# UKU20710_power_board.net
KiCad netlist of a schematic drawn in Altium Designer
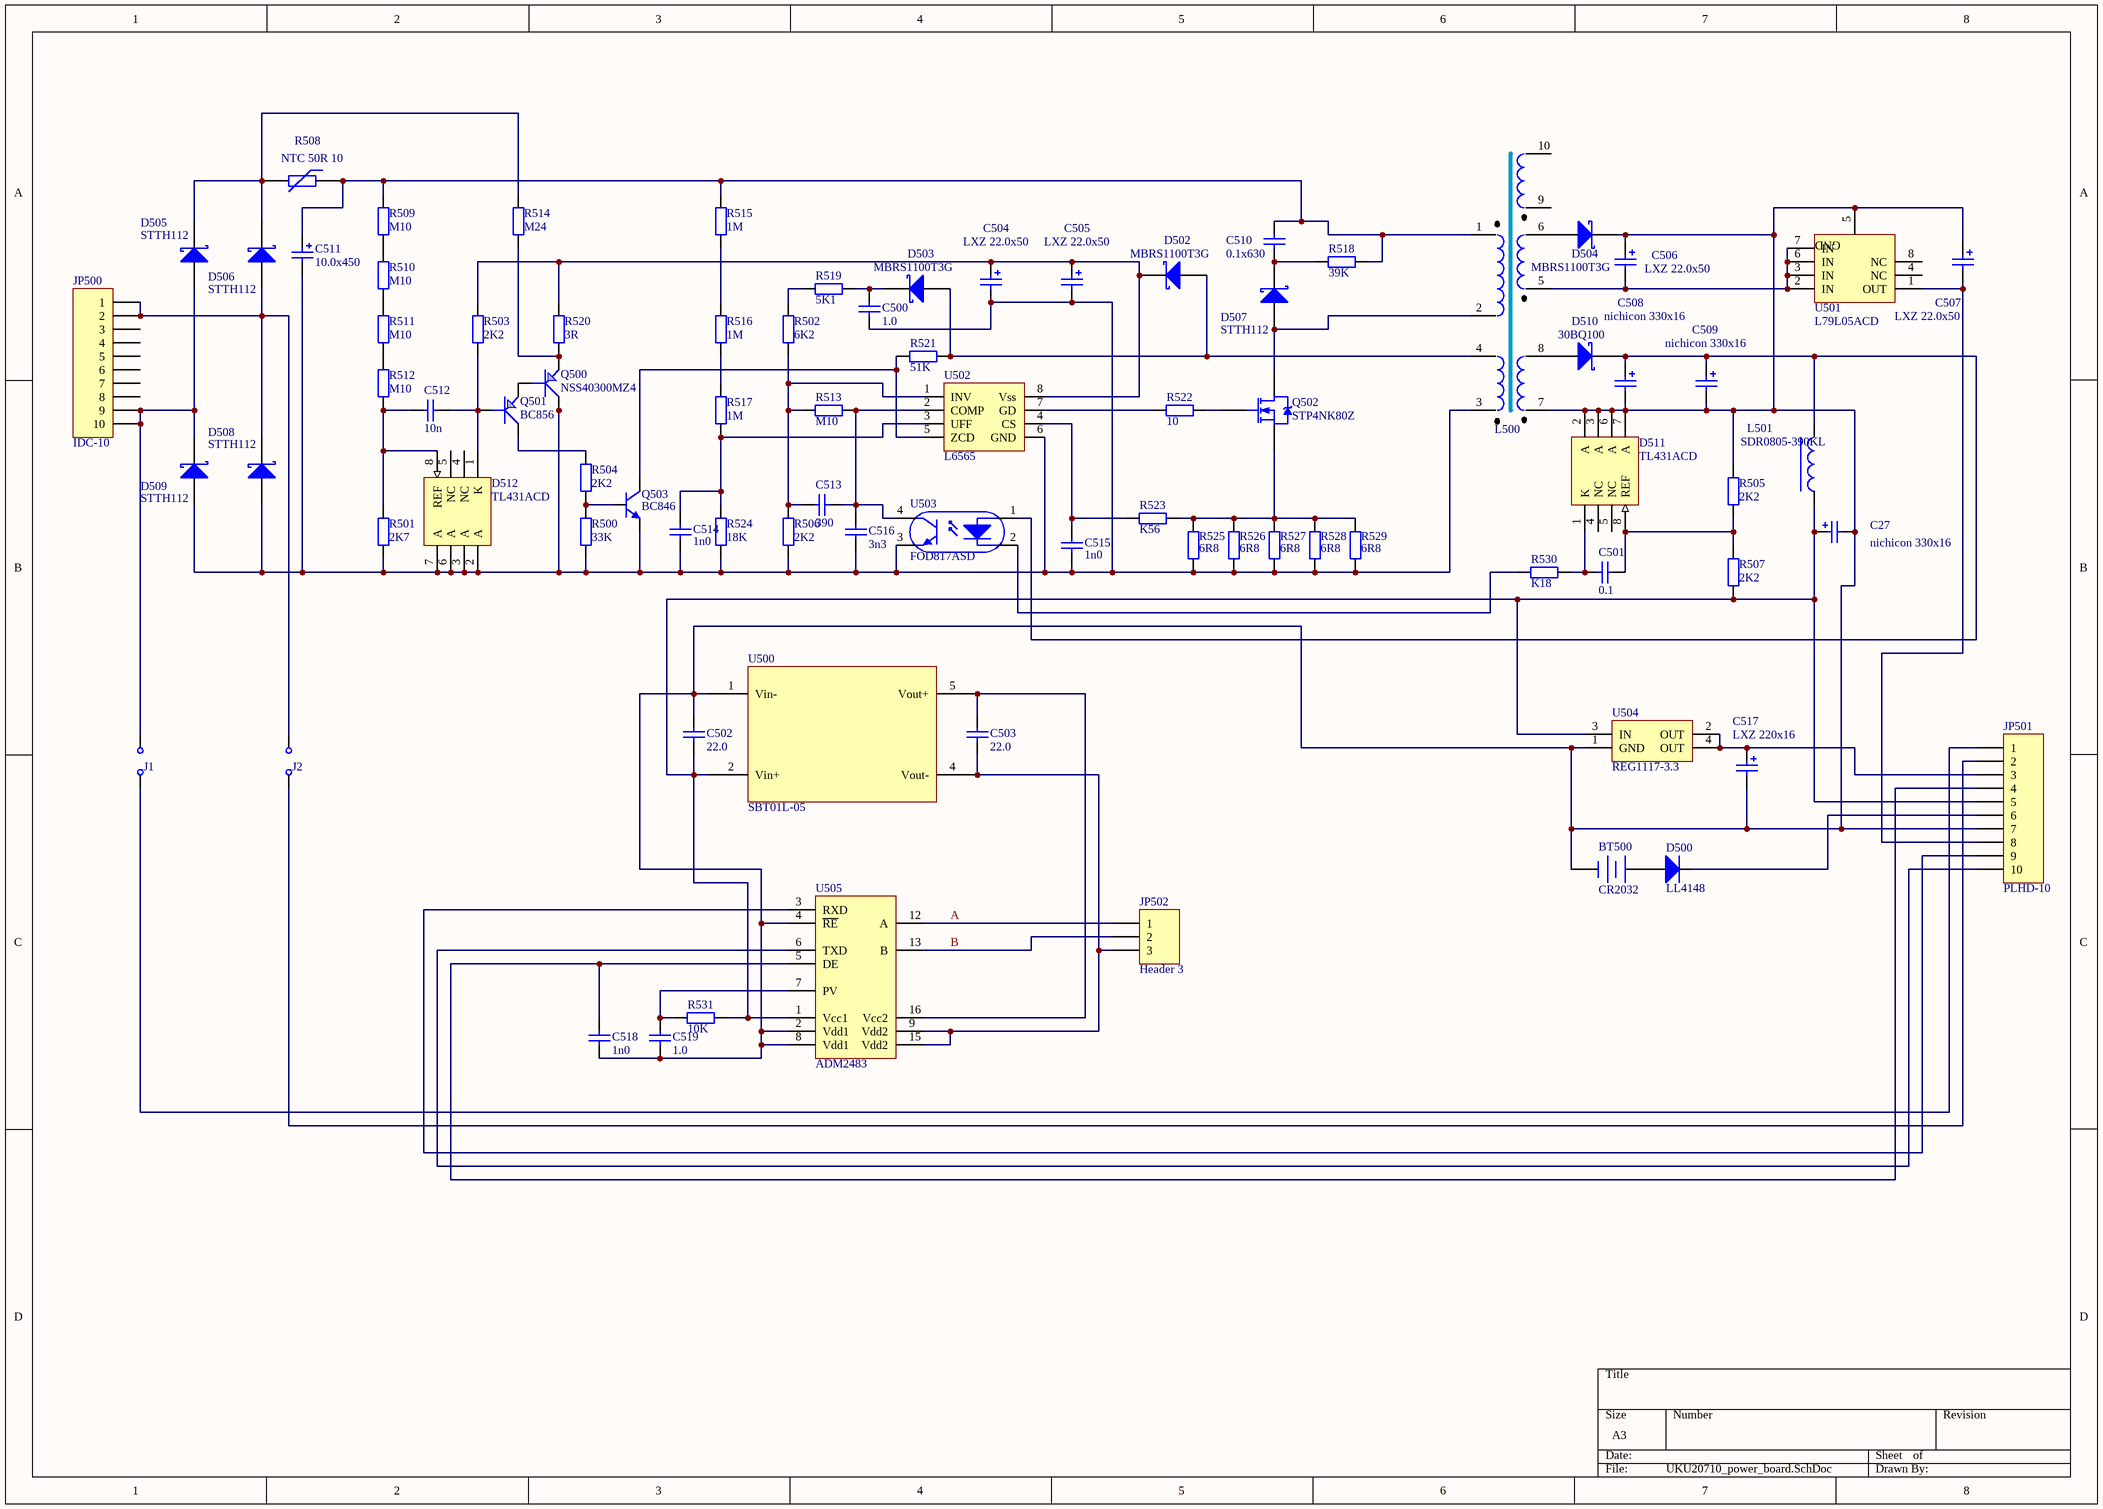
[diagram p0: UKU20710_power_board.SchDoc]

(export (version "E")
  (design (tool "Eeschema 10.0.6"))
  (components
    (comp (ref "BT500")
      (value "CR2032")
      (footprint "BAT_SUPP")
      (description "Multicell Battery")
      (fields (field (name "MANUFACTURER") "Generic Components") (field (name "PUBLISHER") "Altium Limited"))
      (libsource (lib "Miscellaneous Devices") (part "Battery"))
    )
    (comp (ref "C27")
      (value "nichicon 330x16")
      (footprint "el3")
      (description "Polarized Capacitor (Radial)")
      (fields (field (name "MANUFACTURER") "Generic Components") (field (name "PUBLISHER") "Altium Limited"))
      (libsource (lib "PAL") (part "Cap Pol1"))
    )
    (comp (ref "C500")
      (value "1.0")
      (footprint "_1206")
      (description "Capacitor (Semiconductor SIM Model)")
      (fields (field (name "MANUFACTURER") "Generic Components") (field (name "PUBLISHER") "Altium Limited"))
      (libsource (lib "Miscellaneous Devices") (part "Cap Semi"))
    )
    (comp (ref "C501")
      (value "0.1")
      (footprint "_1206")
      (description "Capacitor (Semiconductor SIM Model)")
      (fields (field (name "MANUFACTURER") "Generic Components") (field (name "PUBLISHER") "Altium Limited"))
      (libsource (lib "Miscellaneous Devices") (part "Cap Semi"))
    )
    (comp (ref "C502")
      (value "22.0")
      (footprint "_1206")
      (description "Capacitor (Semiconductor SIM Model)")
      (fields (field (name "MANUFACTURER") "Generic Components") (field (name "PUBLISHER") "Altium Limited"))
      (libsource (lib "Miscellaneous Devices") (part "Cap Semi"))
    )
    (comp (ref "C503")
      (value "22.0")
      (footprint "_1206")
      (description "Capacitor (Semiconductor SIM Model)")
      (fields (field (name "MANUFACTURER") "Generic Components") (field (name "PUBLISHER") "Altium Limited"))
      (libsource (lib "Miscellaneous Devices") (part "Cap Semi"))
    )
    (comp (ref "C504")
      (value "LXZ 22.0x50")
      (footprint "el3")
      (description "Polarized Capacitor (Radial)")
      (fields (field (name "MANUFACTURER") "Generic Components") (field (name "PUBLISHER") "Altium Limited"))
      (libsource (lib "PAL") (part "Cap Pol1"))
    )
    (comp (ref "C505")
      (value "LXZ 22.0x50")
      (footprint "el3")
      (description "Polarized Capacitor (Radial)")
      (fields (field (name "MANUFACTURER") "Generic Components") (field (name "PUBLISHER") "Altium Limited"))
      (libsource (lib "PAL") (part "Cap Pol1"))
    )
    (comp (ref "C506")
      (value "LXZ 22.0x50")
      (footprint "el3")
      (description "Polarized Capacitor (Radial)")
      (fields (field (name "MANUFACTURER") "Generic Components") (field (name "PUBLISHER") "Altium Limited"))
      (libsource (lib "PAL") (part "Cap Pol1"))
    )
    (comp (ref "C507")
      (value "LXZ 22.0x50")
      (footprint "el3")
      (description "Polarized Capacitor (Radial)")
      (fields (field (name "MANUFACTURER") "Generic Components") (field (name "PUBLISHER") "Altium Limited"))
      (libsource (lib "PAL") (part "Cap Pol1"))
    )
    (comp (ref "C508")
      (value "nichicon 330x16")
      (footprint "el3")
      (description "Polarized Capacitor (Radial)")
      (fields (field (name "MANUFACTURER") "Generic Components") (field (name "PUBLISHER") "Altium Limited"))
      (libsource (lib "PAL") (part "Cap Pol1"))
    )
    (comp (ref "C509")
      (value "nichicon 330x16")
      (footprint "el3")
      (description "Polarized Capacitor (Radial)")
      (fields (field (name "MANUFACTURER") "Generic Components") (field (name "PUBLISHER") "Altium Limited"))
      (libsource (lib "PAL") (part "Cap Pol1"))
    )
    (comp (ref "C510")
      (value "0.1x630")
      (footprint "c15")
      (description "Capacitor (Semiconductor SIM Model)")
      (fields (field (name "MANUFACTURER") "Generic Components") (field (name "PUBLISHER") "Altium Limited"))
      (libsource (lib "Miscellaneous Devices") (part "Cap Semi"))
    )
    (comp (ref "C511")
      (value "10.0x450")
      (footprint "el_15_25_h")
      (description "Polarized Capacitor (Radial)")
      (fields (field (name "MANUFACTURER") "Generic Components") (field (name "PUBLISHER") "Altium Limited"))
      (libsource (lib "PAL") (part "Cap Pol1"))
    )
    (comp (ref "C512")
      (value "10n")
      (footprint "_1206")
      (description "Capacitor (Semiconductor SIM Model)")
      (fields (field (name "MANUFACTURER") "Generic Components") (field (name "PUBLISHER") "Altium Limited"))
      (libsource (lib "Miscellaneous Devices") (part "Cap Semi"))
    )
    (comp (ref "C513")
      (value "390")
      (footprint "_1206")
      (description "Capacitor (Semiconductor SIM Model)")
      (fields (field (name "MANUFACTURER") "Generic Components") (field (name "PUBLISHER") "Altium Limited"))
      (libsource (lib "Miscellaneous Devices") (part "Cap Semi"))
    )
    (comp (ref "C514")
      (value "1n0")
      (footprint "_1206")
      (description "Capacitor (Semiconductor SIM Model)")
      (fields (field (name "MANUFACTURER") "Generic Components") (field (name "PUBLISHER") "Altium Limited"))
      (libsource (lib "Miscellaneous Devices") (part "Cap Semi"))
    )
    (comp (ref "C515")
      (value "1n0")
      (footprint "_1206")
      (description "Capacitor (Semiconductor SIM Model)")
      (fields (field (name "MANUFACTURER") "Generic Components") (field (name "PUBLISHER") "Altium Limited"))
      (libsource (lib "Miscellaneous Devices") (part "Cap Semi"))
    )
    (comp (ref "C516")
      (value "3n3")
      (footprint "_1206")
      (description "Capacitor (Semiconductor SIM Model)")
      (fields (field (name "MANUFACTURER") "Generic Components") (field (name "PUBLISHER") "Altium Limited"))
      (libsource (lib "Miscellaneous Devices") (part "Cap Semi"))
    )
    (comp (ref "C517")
      (value "LXZ 220x16")
      (footprint "el3")
      (description "Polarized Capacitor (Radial)")
      (fields (field (name "MANUFACTURER") "Generic Components") (field (name "PUBLISHER") "Altium Limited"))
      (libsource (lib "PAL") (part "Cap Pol1"))
    )
    (comp (ref "C518")
      (value "1n0")
      (footprint "_1206")
      (description "Capacitor (Semiconductor SIM Model)")
      (fields (field (name "MANUFACTURER") "Generic Components") (field (name "PUBLISHER") "Altium Limited"))
      (libsource (lib "Miscellaneous Devices") (part "Cap Semi"))
    )
    (comp (ref "C519")
      (value "1.0")
      (footprint "_1206")
      (description "Capacitor (Semiconductor SIM Model)")
      (fields (field (name "MANUFACTURER") "Generic Components") (field (name "PUBLISHER") "Altium Limited"))
      (libsource (lib "Miscellaneous Devices") (part "Cap Semi"))
    )
    (comp (ref "D500")
      (value "LL4148")
      (footprint "_1206d")
      (description "Default Diode")
      (fields (field (name "MANUFACTURER") "Generic Components") (field (name "PUBLISHER") "Altium Limited"))
      (libsource (lib "PAL") (part "Diode"))
    )
    (comp (ref "D502")
      (value "MBRS1100T3G")
      (footprint "D_6_3")
      (description "Schottky Rectifier")
      (fields
        (field (name "MANUFACTURER") "International Rectifier")
        (field (name "PUBLISHER") "Altium Limited")
      )
      (libsource (lib "IR Discrete Diode") (part "10BQ015"))
    )
    (comp (ref "D503")
      (value "MBRS1100T3G")
      (footprint "D_6_3")
      (description "Schottky Rectifier")
      (fields
        (field (name "MANUFACTURER") "International Rectifier")
        (field (name "PUBLISHER") "Altium Limited")
      )
      (libsource (lib "IR Discrete Diode") (part "10BQ015"))
    )
    (comp (ref "D504")
      (value "MBRS1100T3G")
      (footprint "D_6_3")
      (description "Schottky Rectifier")
      (fields
        (field (name "MANUFACTURER") "International Rectifier")
        (field (name "PUBLISHER") "Altium Limited")
      )
      (libsource (lib "IR Discrete Diode") (part "10BQ015"))
    )
    (comp (ref "D505")
      (value "STTH112")
      (footprint "D_6_3")
      (description "Schottky Diode")
      (fields
        (field (name "MANUFACTURER") "International Rectifier")
        (field (name "PUBLISHER") "Altium Limited")
      )
      (libsource (lib "IR Discrete Diode") (part "10BQ015"))
    )
    (comp (ref "D506")
      (value "STTH112")
      (footprint "D_6_3")
      (description "Schottky Diode")
      (fields
        (field (name "MANUFACTURER") "International Rectifier")
        (field (name "PUBLISHER") "Altium Limited")
      )
      (libsource (lib "IR Discrete Diode") (part "10BQ015"))
    )
    (comp (ref "D507")
      (value "STTH112")
      (footprint "D_6_3")
      (description "Schottky Diode")
      (fields
        (field (name "MANUFACTURER") "International Rectifier")
        (field (name "PUBLISHER") "Altium Limited")
      )
      (libsource (lib "IR Discrete Diode") (part "10BQ015"))
    )
    (comp (ref "D508")
      (value "STTH112")
      (footprint "D_6_3")
      (description "Schottky Diode")
      (fields
        (field (name "MANUFACTURER") "International Rectifier")
        (field (name "PUBLISHER") "Altium Limited")
      )
      (libsource (lib "IR Discrete Diode") (part "10BQ015"))
    )
    (comp (ref "D509")
      (value "STTH112")
      (footprint "D_6_3")
      (description "Schottky Diode")
      (fields
        (field (name "MANUFACTURER") "International Rectifier")
        (field (name "PUBLISHER") "Altium Limited")
      )
      (libsource (lib "IR Discrete Diode") (part "10BQ015"))
    )
    (comp (ref "D510")
      (value "30BQ100")
      (footprint "30BQ100")
      (description "Schottky Rectifier")
      (fields
        (field (name "MANUFACTURER") "International Rectifier")
        (field (name "PUBLISHER") "Altium Limited")
      )
      (libsource (lib "IR Discrete Diode") (part "10BQ015"))
    )
    (comp (ref "D511")
      (value "TL431ACD")
      (footprint "SO-G8")
      (description "Programmable Precision Reference")
      (fields (field (name "MANUFACTURER") "Motorola") (field (name "PUBLISHER") "Altium Limited"))
      (libsource (lib "") (part "TL431ACD_1"))
    )
    (comp (ref "D512")
      (value "TL431ACD")
      (footprint "SO-G8")
      (description "Programmable Precision Reference")
      (fields (field (name "MANUFACTURER") "Motorola") (field (name "PUBLISHER") "Altium Limited"))
      (libsource (lib "Motorola Power Management Voltage Reference") (part "TL431ACD"))
    )
    (comp (ref "J1")
      (value "~")
      (footprint "BT5-2")
      (description "Switch")
      (fields (field (name "MANUFACTURER") "Generic Components") (field (name "PUBLISHER") "Altium Limited"))
      (libsource (lib "PAL") (part "JMP"))
    )
    (comp (ref "J2")
      (value "~")
      (footprint "BT5-2")
      (description "Switch")
      (fields (field (name "MANUFACTURER") "Generic Components") (field (name "PUBLISHER") "Altium Limited"))
      (libsource (lib "PAL") (part "JMP"))
    )
    (comp (ref "JP500")
      (value "IDC-10")
      (footprint "HDR2X5")
      (description "Header, 10-Pin")
      (fields (field (name "MANUFACTURER") "Generic Components") (field (name "PUBLISHER") "Altium Limited"))
      (libsource (lib "") (part "Header 10_1"))
    )
    (comp (ref "JP501")
      (value "PLHD-10")
      (footprint "HDR2X5")
      (description "Header, 10-Pin")
      (fields (field (name "MANUFACTURER") "Generic Components") (field (name "PUBLISHER") "Altium Limited"))
      (libsource (lib "Miscellaneous Connectors") (part "Header 10"))
    )
    (comp (ref "JP502")
      (value "Header 3")
      (footprint "2EDG-5.08-3P")
      (description "Header, 3-Pin")
      (fields (field (name "MANUFACTURER") "Generic Components") (field (name "PUBLISHER") "Altium Limited"))
      (libsource (lib "Miscellaneous Connectors") (part "Header 3"))
    )
    (comp (ref "L500")
      (value "L220-K10")
      (footprint "trans_ring1")
      (description "Дроссель")
      (libsource (lib "PAL") (part "L1_dc_2"))
    )
    (comp (ref "L501")
      (value "SDR0805-390KL")
      (footprint "L10x10")
      (description "Magnetic-Core Inductor")
      (fields (field (name "MANUFACTURER") "Generic Components") (field (name "PUBLISHER") "Altium Limited"))
      (libsource (lib "PAL") (part "Inductor Konstr 2"))
    )
    (comp (ref "Q500")
      (value "NSS40300MZ4")
      (footprint "DSO-G3")
      (libsource (lib "PAL") (part "NSS40300MZ4"))
    )
    (comp (ref "Q501")
      (value "BC856")
      (footprint "SO-G3")
      (description "Bipolar transistor")
      (libsource (lib "MAIN") (part "GT109"))
    )
    (comp (ref "Q502")
      (value "STP4NK80Z")
      (footprint "TO220_h")
      (description "N-Channel Power MOSFET")
      (fields (field (name "MANUFACTURER") "Generic Components") (field (name "PUBLISHER") "Altium Limited"))
      (libsource (lib "Miscellaneous Devices") (part "NMOS-2"))
    )
    (comp (ref "Q503")
      (value "BC846")
      (footprint "SO-G3")
      (description "General Purpose Transistor NPN Silicon")
      (fields (field (name "MANUFACTURER") "Motorola") (field (name "PUBLISHER") "Altium Limited"))
      (libsource (lib "PAL") (part "BC847ALT1"))
    )
    (comp (ref "R500")
      (value "33K")
      (footprint "_1206")
      (description "Resistor")
      (fields (field (name "MANUFACTURER") "Generic Components") (field (name "PUBLISHER") "Altium Limited"))
      (libsource (lib "") (part "Res2_1"))
    )
    (comp (ref "R501")
      (value "2K7")
      (footprint "_1206")
      (description "Resistor")
      (fields (field (name "MANUFACTURER") "Generic Components") (field (name "PUBLISHER") "Altium Limited"))
      (libsource (lib "") (part "Res2_1"))
    )
    (comp (ref "R502")
      (value "6K2")
      (footprint "_1206")
      (description "Resistor")
      (fields (field (name "MANUFACTURER") "Generic Components") (field (name "PUBLISHER") "Altium Limited"))
      (libsource (lib "") (part "Res2_1"))
    )
    (comp (ref "R503")
      (value "2K2")
      (footprint "_1206")
      (description "Resistor")
      (fields (field (name "MANUFACTURER") "Generic Components") (field (name "PUBLISHER") "Altium Limited"))
      (libsource (lib "") (part "Res2_1"))
    )
    (comp (ref "R504")
      (value "2K2")
      (footprint "_1206")
      (description "Resistor")
      (fields (field (name "MANUFACTURER") "Generic Components") (field (name "PUBLISHER") "Altium Limited"))
      (libsource (lib "") (part "Res2_1"))
    )
    (comp (ref "R505")
      (value "2K2")
      (footprint "_1206")
      (description "Resistor")
      (fields (field (name "MANUFACTURER") "Generic Components") (field (name "PUBLISHER") "Altium Limited"))
      (libsource (lib "") (part "Res2_1"))
    )
    (comp (ref "R506")
      (value "2K2")
      (footprint "_1206")
      (description "Resistor")
      (fields (field (name "MANUFACTURER") "Generic Components") (field (name "PUBLISHER") "Altium Limited"))
      (libsource (lib "") (part "Res2_1"))
    )
    (comp (ref "R507")
      (value "2K2")
      (footprint "_1206")
      (description "Resistor")
      (fields (field (name "MANUFACTURER") "Generic Components") (field (name "PUBLISHER") "Altium Limited"))
      (libsource (lib "") (part "Res2_1"))
    )
    (comp (ref "R508")
      (value "NTC 50R 10")
      (footprint "JVR07N")
      (description "Varistor (Voltage-Sensitive Resistor)")
      (fields (field (name "MANUFACTURER") "Generic Components") (field (name "PUBLISHER") "Altium Limited"))
      (libsource (lib "Miscellaneous Devices") (part "Res Varistor"))
    )
    (comp (ref "R509")
      (value "M10")
      (footprint "_1206")
      (description "Resistor")
      (fields (field (name "MANUFACTURER") "Generic Components") (field (name "PUBLISHER") "Altium Limited"))
      (libsource (lib "") (part "Res2_1"))
    )
    (comp (ref "R510")
      (value "M10")
      (footprint "_1206")
      (description "Resistor")
      (fields (field (name "MANUFACTURER") "Generic Components") (field (name "PUBLISHER") "Altium Limited"))
      (libsource (lib "") (part "Res2_1"))
    )
    (comp (ref "R511")
      (value "M10")
      (footprint "_1206")
      (description "Resistor")
      (fields (field (name "MANUFACTURER") "Generic Components") (field (name "PUBLISHER") "Altium Limited"))
      (libsource (lib "") (part "Res2_1"))
    )
    (comp (ref "R512")
      (value "M10")
      (footprint "_1206")
      (description "Resistor")
      (fields (field (name "MANUFACTURER") "Generic Components") (field (name "PUBLISHER") "Altium Limited"))
      (libsource (lib "") (part "Res2_1"))
    )
    (comp (ref "R513")
      (value "M10")
      (footprint "_1206")
      (description "Resistor")
      (fields (field (name "MANUFACTURER") "Generic Components") (field (name "PUBLISHER") "Altium Limited"))
      (libsource (lib "") (part "Res2_2"))
    )
    (comp (ref "R514")
      (value "M24")
      (footprint "AXIAL-0.7")
      (description "Resistor")
      (fields (field (name "MANUFACTURER") "Generic Components") (field (name "PUBLISHER") "Altium Limited"))
      (libsource (lib "") (part "Res2_1"))
    )
    (comp (ref "R515")
      (value "1M")
      (footprint "_1206")
      (description "Resistor")
      (fields (field (name "MANUFACTURER") "Generic Components") (field (name "PUBLISHER") "Altium Limited"))
      (libsource (lib "") (part "Res2_1"))
    )
    (comp (ref "R516")
      (value "1M")
      (footprint "_1206")
      (description "Resistor")
      (fields (field (name "MANUFACTURER") "Generic Components") (field (name "PUBLISHER") "Altium Limited"))
      (libsource (lib "") (part "Res2_1"))
    )
    (comp (ref "R517")
      (value "1M")
      (footprint "_1206")
      (description "Resistor")
      (fields (field (name "MANUFACTURER") "Generic Components") (field (name "PUBLISHER") "Altium Limited"))
      (libsource (lib "") (part "Res2_1"))
    )
    (comp (ref "R518")
      (value "39K")
      (footprint "AXIAL-0.7")
      (description "Resistor")
      (fields (field (name "MANUFACTURER") "Generic Components") (field (name "PUBLISHER") "Altium Limited"))
      (libsource (lib "") (part "Res2_2"))
    )
    (comp (ref "R519")
      (value "5K1")
      (footprint "_1206")
      (description "Resistor")
      (fields (field (name "MANUFACTURER") "Generic Components") (field (name "PUBLISHER") "Altium Limited"))
      (libsource (lib "") (part "Res2_2"))
    )
    (comp (ref "R520")
      (value "3R")
      (footprint "_1206")
      (description "Resistor")
      (fields (field (name "MANUFACTURER") "Generic Components") (field (name "PUBLISHER") "Altium Limited"))
      (libsource (lib "") (part "Res2_1"))
    )
    (comp (ref "R521")
      (value "51K")
      (footprint "_1206")
      (description "Resistor")
      (fields (field (name "MANUFACTURER") "Generic Components") (field (name "PUBLISHER") "Altium Limited"))
      (libsource (lib "") (part "Res2_2"))
    )
    (comp (ref "R522")
      (value "10")
      (footprint "_1206")
      (description "Resistor")
      (fields (field (name "MANUFACTURER") "Generic Components") (field (name "PUBLISHER") "Altium Limited"))
      (libsource (lib "") (part "Res2_2"))
    )
    (comp (ref "R523")
      (value "K56")
      (footprint "_1206")
      (description "Resistor")
      (fields (field (name "MANUFACTURER") "Generic Components") (field (name "PUBLISHER") "Altium Limited"))
      (libsource (lib "") (part "Res2_2"))
    )
    (comp (ref "R524")
      (value "18K")
      (footprint "_1206")
      (description "Resistor")
      (fields (field (name "MANUFACTURER") "Generic Components") (field (name "PUBLISHER") "Altium Limited"))
      (libsource (lib "") (part "Res2_1"))
    )
    (comp (ref "R525")
      (value "6R8")
      (footprint "_1206")
      (description "Resistor")
      (fields (field (name "MANUFACTURER") "Generic Components") (field (name "PUBLISHER") "Altium Limited"))
      (libsource (lib "Miscellaneous Devices") (part "Res2"))
    )
    (comp (ref "R526")
      (value "6R8")
      (footprint "_1206")
      (description "Resistor")
      (fields (field (name "MANUFACTURER") "Generic Components") (field (name "PUBLISHER") "Altium Limited"))
      (libsource (lib "Miscellaneous Devices") (part "Res2"))
    )
    (comp (ref "R527")
      (value "6R8")
      (footprint "_1206")
      (description "Resistor")
      (fields (field (name "MANUFACTURER") "Generic Components") (field (name "PUBLISHER") "Altium Limited"))
      (libsource (lib "Miscellaneous Devices") (part "Res2"))
    )
    (comp (ref "R528")
      (value "6R8")
      (footprint "_1206")
      (description "Resistor")
      (fields (field (name "MANUFACTURER") "Generic Components") (field (name "PUBLISHER") "Altium Limited"))
      (libsource (lib "Miscellaneous Devices") (part "Res2"))
    )
    (comp (ref "R529")
      (value "6R8")
      (footprint "_1206")
      (description "Resistor")
      (fields (field (name "MANUFACTURER") "Generic Components") (field (name "PUBLISHER") "Altium Limited"))
      (libsource (lib "Miscellaneous Devices") (part "Res2"))
    )
    (comp (ref "R530")
      (value "K18")
      (footprint "_1206")
      (description "Resistor")
      (fields (field (name "MANUFACTURER") "Generic Components") (field (name "PUBLISHER") "Altium Limited"))
      (libsource (lib "") (part "Res2_2"))
    )
    (comp (ref "R531")
      (value "10K")
      (footprint "_1206")
      (description "Resistor")
      (fields (field (name "MANUFACTURER") "Generic Components") (field (name "PUBLISHER") "Altium Limited"))
      (libsource (lib "") (part "Res2_2"))
    )
    (comp (ref "U500") (value "SBT01L-05") (footprint "SBT01DET01") (libsource (lib "PAL") (part "SBT01L")))
    (comp (ref "U501")
      (value "L79L05ACD")
      (footprint "SO-G8")
      (description "Negative Voltage Regulator")
      (fields (field (name "MANUFACTURER") "ST-Microelectronics") (field (name "PUBLISHER") "Altium Limited"))
      (libsource (lib "ST Power Mgt Voltage Regulator") (part "L79L05ACD"))
    )
    (comp (ref "U502") (value "L6565") (footprint "so-g8") (libsource (lib "PAL") (part "L6565")))
    (comp (ref "U503") (value "FOD817ASD") (footprint "FOD817ASD") (libsource (lib "PAL") (part "F00817ASD")))
    (comp (ref "U504")
      (value "REG1117-3.3")
      (footprint "DSO-G3")
      (description "800mA and 1A Low Dropout Positive Regulator 2.85V, 3.3V, 5V, and Adjustable")
      (fields (field (name "MANUFACTURER") "Burr-Brown") (field (name "PUBLISHER") "Altium Limited"))
      (libsource (lib "BB Power Mgt Voltage Regulator") (part "REG1117-3.3"))
    )
    (comp (ref "U505") (value "ADM2483") (footprint "SO-G16/D10.4") (libsource (lib "PAL") (part "ADM2483")))
  )
  (nets
    (net (code "1") (name "/A") (class "Default")
      (node (ref "JP502") (pin "1") (pinfunction "1_1") (pintype "passive"))
      (node (ref "U505") (pin "12") (pinfunction "A_12") (pintype "passive"))
    )
    (net (code "2") (name "/B") (class "Default")
      (node (ref "JP502") (pin "2") (pinfunction "2_2") (pintype "passive"))
      (node (ref "U505") (pin "13") (pinfunction "B_13") (pintype "passive"))
    )
    (net (code "3") (name "Net-(BT500-+)") (class "Default")
      (node (ref "BT500") (pin "1") (pinfunction "+_1") (pintype "passive"))
      (node (ref "D500") (pin "1") (pinfunction "A_1") (pintype "passive"))
    )
    (net (code "4") (name "Net-(BT500--)") (class "Default")
      (node (ref "BT500") (pin "2") (pinfunction "-_2") (pintype "passive"))
      (node (ref "C27") (pin "2") (pinfunction "2_2") (pintype "passive"))
      (node (ref "C502") (pin "1") (pinfunction "1_1") (pintype "passive"))
      (node (ref "C506") (pin "1") (pinfunction "1_1") (pintype "passive"))
      (node (ref "C507") (pin "1") (pinfunction "1_1") (pintype "passive"))
      (node (ref "C508") (pin "2") (pinfunction "2_2") (pintype "passive"))
      (node (ref "C509") (pin "2") (pinfunction "2_2") (pintype "passive"))
      (node (ref "C517") (pin "2") (pinfunction "2_2") (pintype "passive"))
      (node (ref "C518") (pin "1") (pinfunction "1_1") (pintype "passive"))
      (node (ref "C519") (pin "1") (pinfunction "1_1") (pintype "passive"))
      (node (ref "D504") (pin "2") (pinfunction "K_2") (pintype "passive"))
      (node (ref "D511") (pin "2") (pinfunction "A_2") (pintype "passive"))
      (node (ref "D511") (pin "3") (pinfunction "A_3") (pintype "passive"))
      (node (ref "D511") (pin "6") (pinfunction "A_6") (pintype "passive"))
      (node (ref "D511") (pin "7") (pinfunction "A_7") (pintype "passive"))
      (node (ref "JP501") (pin "7") (pinfunction "7_7") (pintype "passive"))
      (node (ref "L500") (pin "7") (pintype "passive"))
      (node (ref "R505") (pin "2") (pinfunction "2_2") (pintype "passive"))
      (node (ref "U500") (pin "1") (pinfunction "Vin-_1") (pintype "passive"))
      (node (ref "U501") (pin "5") (pinfunction "GND_5") (pintype "power_in"))
      (node (ref "U504") (pin "1") (pinfunction "GND_1") (pintype "power_in"))
      (node (ref "U505") (pin "2") (pinfunction "Vdd1_2") (pintype "passive"))
      (node (ref "U505") (pin "4") (pinfunction "~{RE}_4") (pintype "passive"))
      (node (ref "U505") (pin "8") (pinfunction "Vdd1_8") (pintype "passive"))
    )
    (net (code "5") (name "Net-(C506-Pad2)") (class "Default")
      (node (ref "C506") (pin "2") (pinfunction "2_2") (pintype "passive"))
      (node (ref "L500") (pin "5") (pintype "passive"))
      (node (ref "U501") (pin "2") (pinfunction "IN_2") (pintype "power_in"))
      (node (ref "U501") (pin "3") (pinfunction "IN_3") (pintype "power_in"))
      (node (ref "U501") (pin "6") (pinfunction "IN_6") (pintype "power_in"))
      (node (ref "U501") (pin "7") (pinfunction "IN_7") (pintype "power_in"))
    )
    (net (code "6") (name "Net-(C510-Pad2)") (class "Default")
      (node (ref "C510") (pin "2") (pinfunction "2_2") (pintype "passive"))
      (node (ref "C511") (pin "1") (pinfunction "1_1") (pintype "passive"))
      (node (ref "L500") (pin "1") (pintype "passive"))
      (node (ref "R508") (pin "1") (pinfunction "1_1") (pintype "passive"))
      (node (ref "R509") (pin "2") (pinfunction "2_2") (pintype "passive"))
      (node (ref "R515") (pin "2") (pinfunction "2_2") (pintype "passive"))
      (node (ref "R518") (pin "1") (pinfunction "1_1") (pintype "passive"))
    )
    (net (code "7") (name "Net-(C517-Pad1)") (class "Default")
      (node (ref "C517") (pin "1") (pinfunction "1_1") (pintype "passive"))
      (node (ref "JP501") (pin "3") (pinfunction "3_3") (pintype "passive"))
      (node (ref "U504") (pin "2") (pinfunction "OUT_2") (pintype "power_in"))
      (node (ref "U504") (pin "4") (pinfunction "OUT_4") (pintype "power_in"))
    )
    (net (code "8") (name "Net-(D500-K)") (class "Default")
      (node (ref "D500") (pin "2") (pinfunction "K_2") (pintype "passive"))
      (node (ref "JP501") (pin "6") (pinfunction "6_6") (pintype "passive"))
    )
    (net (code "9") (name "Net-(D502-A)") (class "Default")
      (node (ref "D502") (pin "1") (pinfunction "A_1") (pintype "passive"))
      (node (ref "D503") (pin "1") (pinfunction "A_1") (pintype "passive"))
      (node (ref "L500") (pin "4") (pintype "passive"))
      (node (ref "R521") (pin "1") (pinfunction "1_1") (pintype "passive"))
    )
    (net (code "10") (name "Net-(D502-K)") (class "Default")
      (node (ref "C504") (pin "1") (pinfunction "1_1") (pintype "passive"))
      (node (ref "C505") (pin "1") (pinfunction "1_1") (pintype "passive"))
      (node (ref "D502") (pin "2") (pinfunction "K_2") (pintype "passive"))
      (node (ref "R503") (pin "2") (pinfunction "2_2") (pintype "passive"))
      (node (ref "R520") (pin "2") (pinfunction "2_2") (pintype "passive"))
      (node (ref "U502") (pin "8") (pinfunction "Vss_8") (pintype "passive"))
    )
    (net (code "11") (name "Net-(D503-K)") (class "Default")
      (node (ref "C500") (pin "2") (pinfunction "2_2") (pintype "passive"))
      (node (ref "D503") (pin "2") (pinfunction "K_2") (pintype "passive"))
      (node (ref "R519") (pin "1") (pinfunction "1_1") (pintype "passive"))
    )
    (net (code "12") (name "Net-(D504-A)") (class "Default")
      (node (ref "D504") (pin "1") (pinfunction "A_1") (pintype "passive"))
      (node (ref "L500") (pin "6") (pintype "passive"))
    )
    (net (code "13") (name "Net-(D505-A)") (class "Default")
      (node (ref "D505") (pin "1") (pinfunction "A_1") (pintype "passive"))
      (node (ref "D509") (pin "2") (pinfunction "K_2") (pintype "passive"))
      (node (ref "J1") (pin "2") (pinfunction "2_2") (pintype "passive"))
      (node (ref "JP500") (pin "10") (pinfunction "10_10") (pintype "passive"))
      (node (ref "JP500") (pin "9") (pinfunction "9_9") (pintype "passive"))
    )
    (net (code "14") (name "Net-(D505-K)") (class "Default")
      (node (ref "D505") (pin "2") (pinfunction "K_2") (pintype "passive"))
      (node (ref "D506") (pin "2") (pinfunction "K_2") (pintype "passive"))
      (node (ref "R508") (pin "2") (pinfunction "2_2") (pintype "passive"))
      (node (ref "R514") (pin "2") (pinfunction "2_2") (pintype "passive"))
    )
    (net (code "15") (name "Net-(D506-A)") (class "Default")
      (node (ref "D506") (pin "1") (pinfunction "A_1") (pintype "passive"))
      (node (ref "D508") (pin "2") (pinfunction "K_2") (pintype "passive"))
      (node (ref "J2") (pin "2") (pinfunction "2_2") (pintype "passive"))
      (node (ref "JP500") (pin "1") (pinfunction "1_1") (pintype "passive"))
      (node (ref "JP500") (pin "2") (pinfunction "2_2") (pintype "passive"))
    )
    (net (code "16") (name "Net-(D507-A)") (class "Default")
      (node (ref "D507") (pin "1") (pinfunction "A_1") (pintype "passive"))
      (node (ref "L500") (pin "2") (pintype "passive"))
      (node (ref "Q502") (pin "2") (pinfunction "D_2") (pintype "passive"))
    )
    (net (code "17") (name "Net-(D507-K)") (class "Default")
      (node (ref "C510") (pin "1") (pinfunction "1_1") (pintype "passive"))
      (node (ref "D507") (pin "2") (pinfunction "K_2") (pintype "passive"))
      (node (ref "R518") (pin "2") (pinfunction "2_2") (pintype "passive"))
    )
    (net (code "18") (name "Net-(D508-A)") (class "Default")
      (node (ref "C500") (pin "1") (pinfunction "1_1") (pintype "passive"))
      (node (ref "C504") (pin "2") (pinfunction "2_2") (pintype "passive"))
      (node (ref "C505") (pin "2") (pinfunction "2_2") (pintype "passive"))
      (node (ref "C511") (pin "2") (pinfunction "2_2") (pintype "passive"))
      (node (ref "C514") (pin "2") (pinfunction "2_2") (pintype "passive"))
      (node (ref "C515") (pin "2") (pinfunction "2_2") (pintype "passive"))
      (node (ref "C516") (pin "1") (pinfunction "1_1") (pintype "passive"))
      (node (ref "D508") (pin "1") (pinfunction "A_1") (pintype "passive"))
      (node (ref "D509") (pin "1") (pinfunction "A_1") (pintype "passive"))
      (node (ref "D512") (pin "2") (pinfunction "A_2") (pintype "passive"))
      (node (ref "D512") (pin "3") (pinfunction "A_3") (pintype "passive"))
      (node (ref "D512") (pin "6") (pinfunction "A_6") (pintype "passive"))
      (node (ref "D512") (pin "7") (pinfunction "A_7") (pintype "passive"))
      (node (ref "L500") (pin "3") (pintype "passive"))
      (node (ref "Q500") (pin "2") (pinfunction "C_2") (pintype "passive"))
      (node (ref "Q500") (pin "4") (pinfunction "C_4") (pintype "passive"))
      (node (ref "Q503") (pin "2") (pinfunction "E_2") (pintype "passive"))
      (node (ref "R500") (pin "1") (pinfunction "1_1") (pintype "passive"))
      (node (ref "R501") (pin "1") (pinfunction "1_1") (pintype "passive"))
      (node (ref "R506") (pin "1") (pinfunction "1_1") (pintype "passive"))
      (node (ref "R524") (pin "1") (pinfunction "1_1") (pintype "passive"))
      (node (ref "R525") (pin "2") (pinfunction "2_2") (pintype "passive"))
      (node (ref "R526") (pin "2") (pinfunction "2_2") (pintype "passive"))
      (node (ref "R527") (pin "2") (pinfunction "2_2") (pintype "passive"))
      (node (ref "R528") (pin "2") (pinfunction "2_2") (pintype "passive"))
      (node (ref "R529") (pin "2") (pinfunction "2_2") (pintype "passive"))
      (node (ref "U502") (pin "6") (pinfunction "GND_6") (pintype "passive"))
      (node (ref "U503") (pin "3") (pinfunction "4_3") (pintype "passive"))
    )
    (net (code "19") (name "Net-(D510-A)") (class "Default")
      (node (ref "D510") (pin "1") (pinfunction "A_1") (pintype "passive"))
      (node (ref "L500") (pin "8") (pintype "passive"))
    )
    (net (code "20") (name "Net-(D510-K)") (class "Default")
      (node (ref "C508") (pin "1") (pinfunction "1_1") (pintype "passive"))
      (node (ref "C509") (pin "1") (pinfunction "1_1") (pintype "passive"))
      (node (ref "D510") (pin "2") (pinfunction "K_2") (pintype "passive"))
      (node (ref "L501") (pin "2") (pinfunction "2_2") (pintype "passive"))
      (node (ref "U503") (pin "1") (pinfunction "0_1") (pintype "passive"))
    )
    (net (code "21") (name "Net-(D511-K)") (class "Default")
      (node (ref "C501") (pin "2") (pinfunction "2_2") (pintype "passive"))
      (node (ref "D511") (pin "1") (pinfunction "K_1") (pintype "passive"))
      (node (ref "R530") (pin "1") (pinfunction "1_1") (pintype "passive"))
    )
    (net (code "22") (name "Net-(D511-REF)") (class "Default")
      (node (ref "C501") (pin "1") (pinfunction "1_1") (pintype "passive"))
      (node (ref "D511") (pin "8") (pinfunction "REF_8") (pintype "input"))
      (node (ref "R505") (pin "1") (pinfunction "1_1") (pintype "passive"))
      (node (ref "R507") (pin "2") (pinfunction "2_2") (pintype "passive"))
    )
    (net (code "23") (name "Net-(D512-K)") (class "Default")
      (node (ref "C512") (pin "1") (pinfunction "1_1") (pintype "passive"))
      (node (ref "D512") (pin "1") (pinfunction "K_1") (pintype "passive"))
      (node (ref "Q501") (pin "1") (pinfunction "B_1") (pintype "passive"))
      (node (ref "R503") (pin "1") (pinfunction "1_1") (pintype "passive"))
    )
    (net (code "24") (name "Net-(D512-REF)") (class "Default")
      (node (ref "C512") (pin "2") (pinfunction "2_2") (pintype "passive"))
      (node (ref "D512") (pin "8") (pinfunction "REF_8") (pintype "input"))
      (node (ref "R501") (pin "2") (pinfunction "2_2") (pintype "passive"))
      (node (ref "R512") (pin "1") (pinfunction "1_1") (pintype "passive"))
    )
    (net (code "25") (name "Net-(J1-Pad1)") (class "Default")
      (node (ref "J1") (pin "1") (pinfunction "1_1") (pintype "passive"))
      (node (ref "JP501") (pin "1") (pinfunction "1_1") (pintype "passive"))
    )
    (net (code "26") (name "Net-(J2-Pad1)") (class "Default")
      (node (ref "J2") (pin "1") (pinfunction "1_1") (pintype "passive"))
      (node (ref "JP501") (pin "2") (pinfunction "2_2") (pintype "passive"))
    )
    (net (code "27") (name "Net-(Q500-B)") (class "Default")
      (node (ref "Q500") (pin "1") (pinfunction "B_1") (pintype "passive"))
      (node (ref "Q501") (pin "2") (pinfunction "E_2") (pintype "passive"))
    )
    (net (code "28") (name "Net-(Q500-E)") (class "Default")
      (node (ref "Q500") (pin "3") (pinfunction "E_3") (pintype "passive"))
      (node (ref "R514") (pin "1") (pinfunction "1_1") (pintype "passive"))
      (node (ref "R520") (pin "1") (pinfunction "1_1") (pintype "passive"))
    )
    (net (code "29") (name "Net-(Q501-C)") (class "Default")
      (node (ref "Q501") (pin "3") (pinfunction "C_3") (pintype "passive"))
      (node (ref "R504") (pin "2") (pinfunction "2_2") (pintype "passive"))
    )
    (net (code "30") (name "Net-(Q502-G)") (class "Default")
      (node (ref "Q502") (pin "1") (pinfunction "G_1") (pintype "passive"))
      (node (ref "R522") (pin "1") (pinfunction "1_1") (pintype "passive"))
    )
    (net (code "31") (name "Net-(Q502-S)") (class "Default")
      (node (ref "Q502") (pin "3") (pinfunction "S_3") (pintype "passive"))
      (node (ref "R523") (pin "1") (pinfunction "1_1") (pintype "passive"))
      (node (ref "R525") (pin "1") (pinfunction "1_1") (pintype "passive"))
      (node (ref "R526") (pin "1") (pinfunction "1_1") (pintype "passive"))
      (node (ref "R527") (pin "1") (pinfunction "1_1") (pintype "passive"))
      (node (ref "R528") (pin "1") (pinfunction "1_1") (pintype "passive"))
      (node (ref "R529") (pin "1") (pinfunction "1_1") (pintype "passive"))
    )
    (net (code "32") (name "Net-(Q503-B)") (class "Default")
      (node (ref "Q503") (pin "1") (pinfunction "B_1") (pintype "passive"))
      (node (ref "R500") (pin "2") (pinfunction "2_2") (pintype "passive"))
      (node (ref "R504") (pin "1") (pinfunction "1_1") (pintype "passive"))
    )
    (net (code "33") (name "Net-(Q503-C)") (class "Default")
      (node (ref "Q503") (pin "3") (pinfunction "C_3") (pintype "passive"))
      (node (ref "R521") (pin "2") (pinfunction "2_2") (pintype "passive"))
      (node (ref "U502") (pin "5") (pinfunction "ZCD_5") (pintype "passive"))
    )
    (net (code "34") (name "Net-(R502-Pad2)") (class "Default")
      (node (ref "R502") (pin "2") (pinfunction "2_2") (pintype "passive"))
      (node (ref "R519") (pin "2") (pinfunction "2_2") (pintype "passive"))
    )
    (net (code "35") (name "Net-(R509-Pad1)") (class "Default")
      (node (ref "R509") (pin "1") (pinfunction "1_1") (pintype "passive"))
      (node (ref "R510") (pin "2") (pinfunction "2_2") (pintype "passive"))
    )
    (net (code "36") (name "Net-(R510-Pad1)") (class "Default")
      (node (ref "R510") (pin "1") (pinfunction "1_1") (pintype "passive"))
      (node (ref "R511") (pin "2") (pinfunction "2_2") (pintype "passive"))
    )
    (net (code "37") (name "Net-(R511-Pad1)") (class "Default")
      (node (ref "R511") (pin "1") (pinfunction "1_1") (pintype "passive"))
      (node (ref "R512") (pin "2") (pinfunction "2_2") (pintype "passive"))
    )
    (net (code "38") (name "Net-(R515-Pad1)") (class "Default")
      (node (ref "R515") (pin "1") (pinfunction "1_1") (pintype "passive"))
      (node (ref "R516") (pin "2") (pinfunction "2_2") (pintype "passive"))
    )
    (net (code "39") (name "Net-(R516-Pad1)") (class "Default")
      (node (ref "R516") (pin "1") (pinfunction "1_1") (pintype "passive"))
      (node (ref "R517") (pin "2") (pinfunction "2_2") (pintype "passive"))
    )
    (net (code "40") (name "Net-(U500-Vin+)") (class "Default")
      (node (ref "C27") (pin "1") (pinfunction "1_1") (pintype "passive"))
      (node (ref "C502") (pin "2") (pinfunction "2_2") (pintype "passive"))
      (node (ref "JP501") (pin "5") (pinfunction "5_5") (pintype "passive"))
      (node (ref "L501") (pin "1") (pinfunction "1_1") (pintype "passive"))
      (node (ref "R507") (pin "1") (pinfunction "1_1") (pintype "passive"))
      (node (ref "R531") (pin "1") (pinfunction "1_1") (pintype "passive"))
      (node (ref "U500") (pin "2") (pinfunction "Vin+_2") (pintype "passive"))
      (node (ref "U504") (pin "3") (pinfunction "IN_3") (pintype "power_in"))
      (node (ref "U505") (pin "1") (pinfunction "Vcc1_1") (pintype "passive"))
    )
    (net (code "41") (name "Net-(U500-Vout+)") (class "Default")
      (node (ref "C503") (pin "1") (pinfunction "1_1") (pintype "passive"))
      (node (ref "U500") (pin "5") (pinfunction "Vout+_5") (pintype "passive"))
      (node (ref "U505") (pin "16") (pinfunction "Vcc2_16") (pintype "passive"))
    )
    (net (code "42") (name "Net-(U500-Vout-)") (class "Default")
      (node (ref "C503") (pin "2") (pinfunction "2_2") (pintype "passive"))
      (node (ref "JP502") (pin "3") (pinfunction "3_3") (pintype "passive"))
      (node (ref "U500") (pin "4") (pinfunction "Vout-_4") (pintype "passive"))
      (node (ref "U505") (pin "15") (pinfunction "Vdd2_15") (pintype "passive"))
      (node (ref "U505") (pin "9") (pinfunction "Vdd2_9") (pintype "passive"))
    )
    (net (code "43") (name "Net-(U501-OUT)") (class "Default")
      (node (ref "C507") (pin "2") (pinfunction "2_2") (pintype "passive"))
      (node (ref "JP501") (pin "8") (pinfunction "8_8") (pintype "passive"))
      (node (ref "U501") (pin "1") (pinfunction "OUT_1") (pintype "power_in"))
    )
    (net (code "44") (name "Net-(U502-COMP)") (class "Default")
      (node (ref "C513") (pin "2") (pinfunction "2_2") (pintype "passive"))
      (node (ref "C516") (pin "2") (pinfunction "2_2") (pintype "passive"))
      (node (ref "R513") (pin "1") (pinfunction "1_1") (pintype "passive"))
      (node (ref "U502") (pin "2") (pinfunction "COMP_2") (pintype "passive"))
      (node (ref "U503") (pin "4") (pinfunction "2_4") (pintype "passive"))
    )
    (net (code "45") (name "Net-(U502-CS)") (class "Default")
      (node (ref "C515") (pin "1") (pinfunction "1_1") (pintype "passive"))
      (node (ref "R523") (pin "2") (pinfunction "2_2") (pintype "passive"))
      (node (ref "U502") (pin "4") (pinfunction "CS_4") (pintype "passive"))
    )
    (net (code "46") (name "Net-(U502-GD)") (class "Default")
      (node (ref "R522") (pin "2") (pinfunction "2_2") (pintype "passive"))
      (node (ref "U502") (pin "7") (pinfunction "GD_7") (pintype "passive"))
    )
    (net (code "47") (name "Net-(U502-INV)") (class "Default")
      (node (ref "C513") (pin "1") (pinfunction "1_1") (pintype "passive"))
      (node (ref "R502") (pin "1") (pinfunction "1_1") (pintype "passive"))
      (node (ref "R506") (pin "2") (pinfunction "2_2") (pintype "passive"))
      (node (ref "R513") (pin "2") (pinfunction "2_2") (pintype "passive"))
      (node (ref "U502") (pin "1") (pinfunction "INV_1") (pintype "passive"))
    )
    (net (code "48") (name "Net-(U502-UFF)") (class "Default")
      (node (ref "C514") (pin "1") (pinfunction "1_1") (pintype "passive"))
      (node (ref "R517") (pin "1") (pinfunction "1_1") (pintype "passive"))
      (node (ref "R524") (pin "2") (pinfunction "2_2") (pintype "passive"))
      (node (ref "U502") (pin "3") (pinfunction "UFF_3") (pintype "passive"))
    )
    (net (code "49") (name "Net-(U503-1)") (class "Default")
      (node (ref "R530") (pin "2") (pinfunction "2_2") (pintype "passive"))
      (node (ref "U503") (pin "2") (pinfunction "1_2") (pintype "passive"))
    )
    (net (code "50") (name "Net-(U505-DE)") (class "Default")
      (node (ref "C518") (pin "2") (pinfunction "2_2") (pintype "passive"))
      (node (ref "JP501") (pin "4") (pinfunction "4_4") (pintype "passive"))
      (node (ref "U505") (pin "5") (pinfunction "DE_5") (pintype "passive"))
    )
    (net (code "51") (name "Net-(U505-PV)") (class "Default")
      (node (ref "C519") (pin "2") (pinfunction "2_2") (pintype "passive"))
      (node (ref "R531") (pin "2") (pinfunction "2_2") (pintype "passive"))
      (node (ref "U505") (pin "7") (pinfunction "PV_7") (pintype "passive"))
    )
    (net (code "52") (name "Net-(U505-RXD)") (class "Default")
      (node (ref "JP501") (pin "9") (pinfunction "9_9") (pintype "passive"))
      (node (ref "U505") (pin "3") (pinfunction "RXD_3") (pintype "passive"))
    )
    (net (code "53") (name "Net-(U505-TXD)") (class "Default")
      (node (ref "JP501") (pin "10") (pinfunction "10_10") (pintype "passive"))
      (node (ref "U505") (pin "6") (pinfunction "TXD_6") (pintype "passive"))
    )
    (net (code "54") (name "unconnected-(D511-NC-Pad4)") (class "Default")
      (node (ref "D511") (pin "4") (pinfunction "NC_4") (pintype "passive"))
    )
    (net (code "55") (name "unconnected-(D511-NC-Pad5)") (class "Default")
      (node (ref "D511") (pin "5") (pinfunction "NC_5") (pintype "passive"))
    )
    (net (code "56") (name "unconnected-(D512-NC-Pad4)") (class "Default")
      (node (ref "D512") (pin "4") (pinfunction "NC_4") (pintype "passive"))
    )
    (net (code "57") (name "unconnected-(D512-NC-Pad5)") (class "Default")
      (node (ref "D512") (pin "5") (pinfunction "NC_5") (pintype "passive"))
    )
    (net (code "58") (name "unconnected-(JP500-Pad3)") (class "Default")
      (node (ref "JP500") (pin "3") (pinfunction "3_3") (pintype "passive"))
    )
    (net (code "59") (name "unconnected-(JP500-Pad4)") (class "Default")
      (node (ref "JP500") (pin "4") (pinfunction "4_4") (pintype "passive"))
    )
    (net (code "60") (name "unconnected-(JP500-Pad5)") (class "Default")
      (node (ref "JP500") (pin "5") (pinfunction "5_5") (pintype "passive"))
    )
    (net (code "61") (name "unconnected-(JP500-Pad6)") (class "Default")
      (node (ref "JP500") (pin "6") (pinfunction "6_6") (pintype "passive"))
    )
    (net (code "62") (name "unconnected-(JP500-Pad7)") (class "Default")
      (node (ref "JP500") (pin "7") (pinfunction "7_7") (pintype "passive"))
    )
    (net (code "63") (name "unconnected-(JP500-Pad8)") (class "Default")
      (node (ref "JP500") (pin "8") (pinfunction "8_8") (pintype "passive"))
    )
    (net (code "64") (name "unconnected-(L500-Pad9)") (class "Default")
      (node (ref "L500") (pin "9") (pintype "passive"))
    )
    (net (code "65") (name "unconnected-(L500-Pad10)") (class "Default")
      (node (ref "L500") (pin "10") (pinfunction "10_10") (pintype "passive"))
    )
    (net (code "66") (name "unconnected-(U501-NC-Pad4)") (class "Default")
      (node (ref "U501") (pin "4") (pinfunction "NC_4") (pintype "passive"))
    )
    (net (code "67") (name "unconnected-(U501-NC-Pad8)") (class "Default")
      (node (ref "U501") (pin "8") (pinfunction "NC_8") (pintype "passive"))
    )
  )
)
